# EVB-ANNA-B5_SCHEM_0002_ANNA_Module.net
KiCad netlist of a schematic drawn in Altium Designer
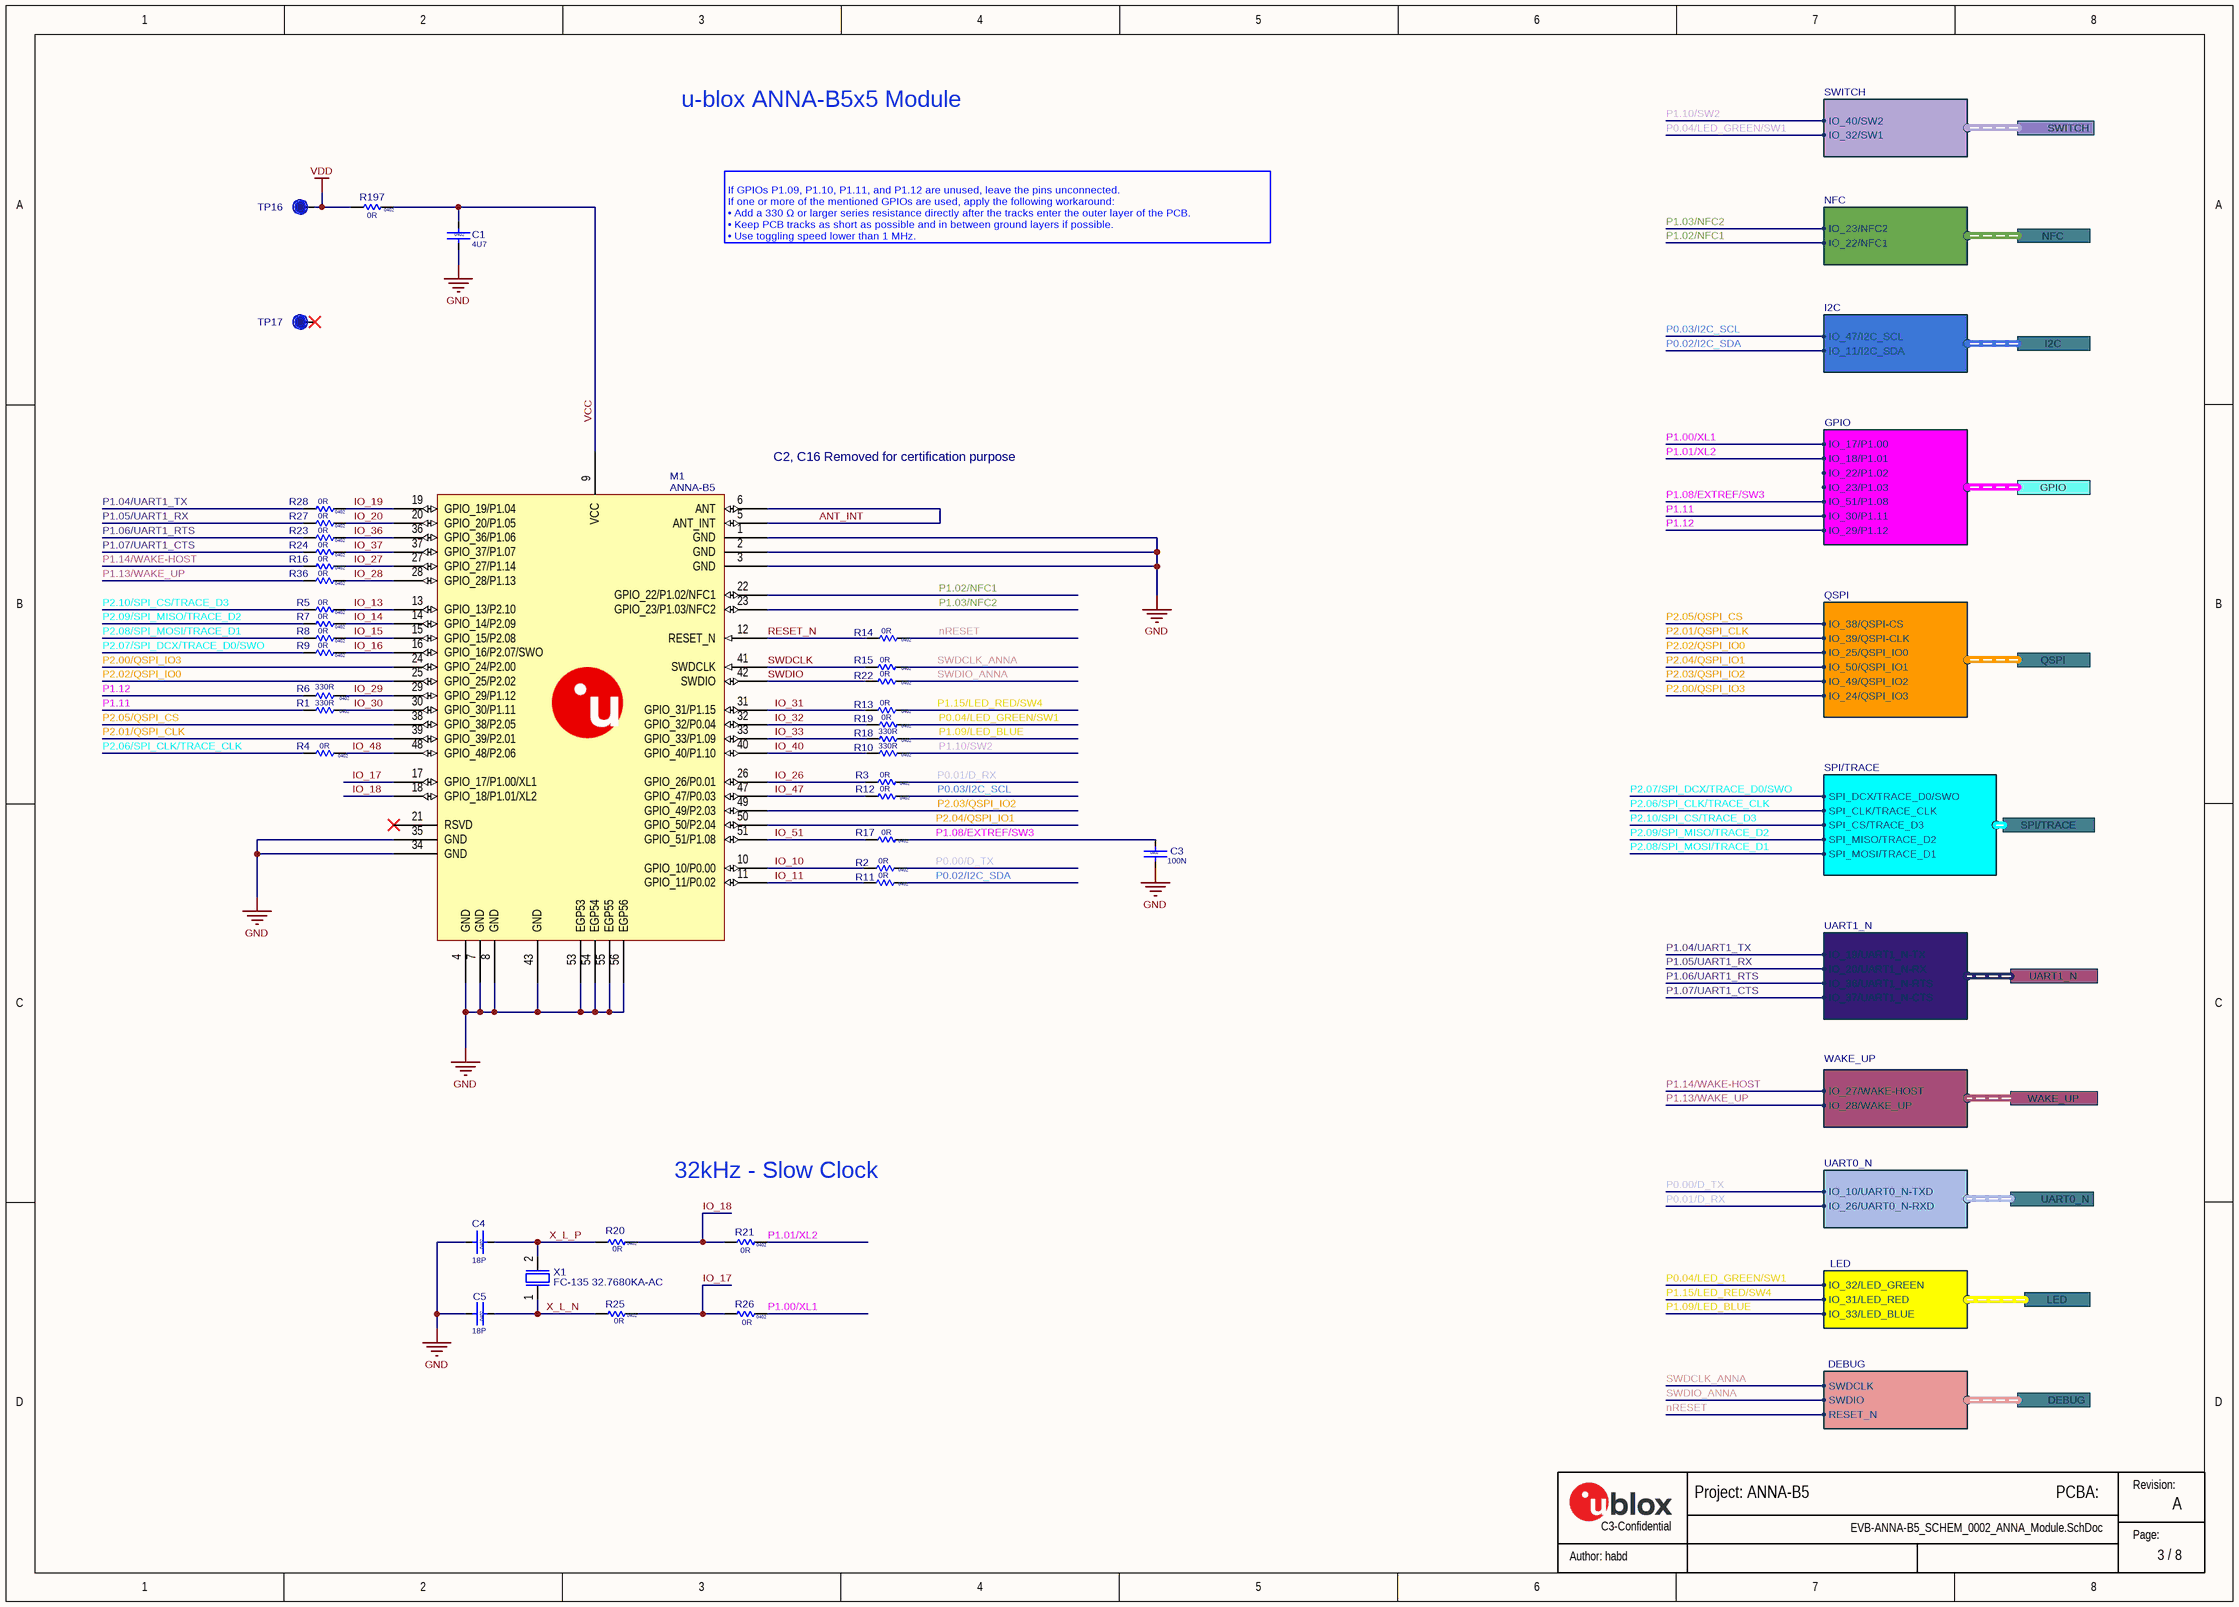
[diagram p0: EVB-ANNA-B5_SCHEM_0002_ANNA_Module.SchDoc]

(export (version "E")
  (design (tool "Eeschema 10.0.6"))
  (components
    (comp (ref "C1")
      (value "4U7")
      (footprint "Cap 0402 HD")
      (description "CAP CER X5R 0402 4U7 20% 10V")
      (fields
        (field (name "SIZE") "0402")
        (field (name "PART NUMBER") "UBXH01-0000243")
        (field (name "TOLERANCE") "20%")
        (field (name "EDITOR") "martin.pilik")
        (field (name "RELEASED BY") "fabrice.bret-dibat")
      )
      (libsource (lib "UBX_Parts_DB_Lib") (part "Cap Chip"))
    )
    (comp (ref "C3")
      (value "100N")
      (footprint "Cap 0402 HD")
      (description "CAP CER X5R 0402 100N 10% 10V")
      (fields
        (field (name "SIZE") "0402")
        (field (name "PART NUMBER") "UBXH01-2021002")
        (field (name "TOLERANCE") "10%")
        (field (name "EDITOR") "roland.rust")
        (field (name "RELEASED BY") "roland.rust")
      )
      (libsource (lib "UBX_Parts_DB_Lib") (part "Cap Chip"))
    )
    (comp (ref "C4")
      (value "18P")
      (footprint "Cap_0402_1100Lx600Wx600H_600x600Pad_350G_FLX")
      (description "CAP CER C0G 0402 18P 5% 25V")
      (fields
        (field (name "SIZE") "0402")
        (field (name "PART NUMBER") "UBXH01-0004017")
        (field (name "TOLERANCE") "5%")
        (field (name "EDITOR") "doris.zahnd")
        (field (name "RELEASED BY") "daniel.hurni")
      )
      (libsource (lib "UBX_Parts_DB_Lib") (part "Cap Chip"))
    )
    (comp (ref "C5")
      (value "18P")
      (footprint "Cap_0402_1100Lx600Wx600H_600x600Pad_350G_FLX")
      (description "CAP CER C0G 0402 18P 5% 25V")
      (fields
        (field (name "SIZE") "0402")
        (field (name "PART NUMBER") "UBXH01-0004017")
        (field (name "TOLERANCE") "5%")
        (field (name "EDITOR") "doris.zahnd")
        (field (name "RELEASED BY") "daniel.hurni")
      )
      (libsource (lib "UBX_Parts_DB_Lib") (part "Cap Chip"))
    )
    (comp (ref "M1")
      (value "UBXH29-0000036")
      (footprint "ANNA-B5")
      (description "SHORT RANGE BLE AND IEEE802.15.4 SIP MODULE U-BLOX ANNA-B5")
      (fields
        (field (name "MANUFACTURER") "u-blox")
        (field (name "MANUFACTURER P/N") "ANNA-B5")
        (field (name "OWNER") "Yaqin Chen")
      )
      (libsource (lib "UBX_Arena") (part "ANNA-B5"))
    )
    (comp (ref "R1")
      (value "330R")
      (footprint "RES_0402_1100Lx600Wx400H_500x600Pad_400G_FLX")
      (description "RES THICK FILM CHIP 0402 330R 5% 63mW")
      (fields
        (field (name "SIZE") "0402")
        (field (name "PART NUMBER") "UBXH18-0008037")
        (field (name "TOLERANCE") "5%")
        (field (name "EDITOR") "daniel.hurni")
        (field (name "RELEASED BY") "doris.zahnd")
      )
      (libsource (lib "UBX_Parts_DB_Lib") (part "Res sm"))
    )
    (comp (ref "R2")
      (value "0R")
      (footprint "RES 0402 HD")
      (description "RES THICK FILM CHIP 0402 0R 0 100mW")
      (fields
        (field (name "SIZE") "0402")
        (field (name "PART NUMBER") "UBXH18-0003002")
        (field (name "TOLERANCE") "0")
        (field (name "EDITOR") "charlotte.biber")
        (field (name "RELEASED BY") "peter.mueller")
      )
      (libsource (lib "UBX_Parts_DB_Lib") (part "Res sm"))
    )
    (comp (ref "R3")
      (value "0R")
      (footprint "RES 0402 HD")
      (description "RES THICK FILM CHIP 0402 0R 0 100mW")
      (fields
        (field (name "SIZE") "0402")
        (field (name "PART NUMBER") "UBXH18-0003002")
        (field (name "TOLERANCE") "0")
        (field (name "EDITOR") "charlotte.biber")
        (field (name "RELEASED BY") "peter.mueller")
      )
      (libsource (lib "UBX_Parts_DB_Lib") (part "Res sm"))
    )
    (comp (ref "R4")
      (value "0R")
      (footprint "RES 0402 HD")
      (description "RES THICK FILM CHIP 0402 0R 0 100mW")
      (fields
        (field (name "SIZE") "0402")
        (field (name "PART NUMBER") "UBXH18-0003002")
        (field (name "TOLERANCE") "0")
        (field (name "EDITOR") "charlotte.biber")
        (field (name "RELEASED BY") "peter.mueller")
      )
      (libsource (lib "UBX_Parts_DB_Lib") (part "Res sm"))
    )
    (comp (ref "R5")
      (value "0R")
      (footprint "RES 0402 HD")
      (description "RES THICK FILM CHIP 0402 0R 0 100mW")
      (fields
        (field (name "SIZE") "0402")
        (field (name "PART NUMBER") "UBXH18-0003002")
        (field (name "TOLERANCE") "0")
        (field (name "EDITOR") "charlotte.biber")
        (field (name "RELEASED BY") "peter.mueller")
      )
      (libsource (lib "UBX_Parts_DB_Lib") (part "Res sm"))
    )
    (comp (ref "R6")
      (value "330R")
      (footprint "RES_0402_1100Lx600Wx400H_500x600Pad_400G_FLX")
      (description "RES THICK FILM CHIP 0402 330R 5% 63mW")
      (fields
        (field (name "SIZE") "0402")
        (field (name "PART NUMBER") "UBXH18-0008037")
        (field (name "TOLERANCE") "5%")
        (field (name "EDITOR") "daniel.hurni")
        (field (name "RELEASED BY") "doris.zahnd")
      )
      (libsource (lib "UBX_Parts_DB_Lib") (part "Res sm"))
    )
    (comp (ref "R7")
      (value "0R")
      (footprint "RES 0402 HD")
      (description "RES THICK FILM CHIP 0402 0R 0 100mW")
      (fields
        (field (name "SIZE") "0402")
        (field (name "PART NUMBER") "UBXH18-0003002")
        (field (name "TOLERANCE") "0")
        (field (name "EDITOR") "charlotte.biber")
        (field (name "RELEASED BY") "peter.mueller")
      )
      (libsource (lib "UBX_Parts_DB_Lib") (part "Res sm"))
    )
    (comp (ref "R8")
      (value "0R")
      (footprint "RES 0402 HD")
      (description "RES THICK FILM CHIP 0402 0R 0 100mW")
      (fields
        (field (name "SIZE") "0402")
        (field (name "PART NUMBER") "UBXH18-0003002")
        (field (name "TOLERANCE") "0")
        (field (name "EDITOR") "charlotte.biber")
        (field (name "RELEASED BY") "peter.mueller")
      )
      (libsource (lib "UBX_Parts_DB_Lib") (part "Res sm"))
    )
    (comp (ref "R9")
      (value "0R")
      (footprint "RES 0402 HD")
      (description "RES THICK FILM CHIP 0402 0R 0 100mW")
      (fields
        (field (name "SIZE") "0402")
        (field (name "PART NUMBER") "UBXH18-0003002")
        (field (name "TOLERANCE") "0")
        (field (name "EDITOR") "charlotte.biber")
        (field (name "RELEASED BY") "peter.mueller")
      )
      (libsource (lib "UBX_Parts_DB_Lib") (part "Res sm"))
    )
    (comp (ref "R10")
      (value "330R")
      (footprint "RES_0402_1100Lx600Wx400H_500x600Pad_400G_FLX")
      (description "RES THICK FILM CHIP 0402 330R 5% 63mW")
      (fields
        (field (name "SIZE") "0402")
        (field (name "PART NUMBER") "UBXH18-0008037")
        (field (name "TOLERANCE") "5%")
        (field (name "EDITOR") "daniel.hurni")
        (field (name "RELEASED BY") "doris.zahnd")
      )
      (libsource (lib "UBX_Parts_DB_Lib") (part "Res sm"))
    )
    (comp (ref "R11")
      (value "0R")
      (footprint "RES 0402 HD")
      (description "RES THICK FILM CHIP 0402 0R 0 100mW")
      (fields
        (field (name "SIZE") "0402")
        (field (name "PART NUMBER") "UBXH18-0003002")
        (field (name "TOLERANCE") "0")
        (field (name "EDITOR") "charlotte.biber")
        (field (name "RELEASED BY") "peter.mueller")
      )
      (libsource (lib "UBX_Parts_DB_Lib") (part "Res sm"))
    )
    (comp (ref "R12")
      (value "0R")
      (footprint "RES_0402_1100Lx600Wx400H_500x600Pad_400G_FLX")
      (description "RES THICK FILM CHIP 0402 0R 0 100mW")
      (fields
        (field (name "SIZE") "0402")
        (field (name "PART NUMBER") "UBXH18-0003002")
        (field (name "TOLERANCE") "0")
        (field (name "EDITOR") "charlotte.biber")
        (field (name "RELEASED BY") "peter.mueller")
      )
      (libsource (lib "UBX_Parts_DB_Lib") (part "Res sm"))
    )
    (comp (ref "R13")
      (value "0R")
      (footprint "RES_0402_1100Lx600Wx400H_500x600Pad_400G_FLX")
      (description "RES THICK FILM CHIP 0402 0R 0 100mW")
      (fields
        (field (name "SIZE") "0402")
        (field (name "PART NUMBER") "UBXH18-0003002")
        (field (name "TOLERANCE") "0")
        (field (name "EDITOR") "charlotte.biber")
        (field (name "RELEASED BY") "peter.mueller")
      )
      (libsource (lib "UBX_Parts_DB_Lib") (part "Res sm"))
    )
    (comp (ref "R14")
      (value "0R")
      (footprint "RES_0402_1100Lx600Wx400H_500x600Pad_400G_FLX")
      (description "RES THICK FILM CHIP 0402 0R 0 100mW")
      (fields
        (field (name "SIZE") "0402")
        (field (name "PART NUMBER") "UBXH18-0003002")
        (field (name "TOLERANCE") "0")
        (field (name "EDITOR") "charlotte.biber")
        (field (name "RELEASED BY") "peter.mueller")
      )
      (libsource (lib "UBX_Parts_DB_Lib") (part "Res sm"))
    )
    (comp (ref "R15")
      (value "0R")
      (footprint "RES 0402 HD")
      (description "RES THICK FILM CHIP 0402 0R 0 100mW")
      (fields
        (field (name "SIZE") "0402")
        (field (name "PART NUMBER") "UBXH18-0003002")
        (field (name "TOLERANCE") "0")
        (field (name "EDITOR") "charlotte.biber")
        (field (name "RELEASED BY") "peter.mueller")
      )
      (libsource (lib "UBX_Parts_DB_Lib") (part "Res sm"))
    )
    (comp (ref "R16")
      (value "0R")
      (footprint "RES 0402 HD")
      (description "RES THICK FILM CHIP 0402 0R 0 100mW")
      (fields
        (field (name "SIZE") "0402")
        (field (name "PART NUMBER") "UBXH18-0003002")
        (field (name "TOLERANCE") "0")
        (field (name "EDITOR") "charlotte.biber")
        (field (name "RELEASED BY") "peter.mueller")
      )
      (libsource (lib "UBX_Parts_DB_Lib") (part "Res sm"))
    )
    (comp (ref "R17")
      (value "0R")
      (footprint "RES 0402 HD")
      (description "RES THICK FILM CHIP 0402 0R 0 100mW")
      (fields
        (field (name "SIZE") "0402")
        (field (name "PART NUMBER") "UBXH18-0003002")
        (field (name "TOLERANCE") "0")
        (field (name "EDITOR") "charlotte.biber")
        (field (name "RELEASED BY") "peter.mueller")
      )
      (libsource (lib "UBX_Parts_DB_Lib") (part "Res sm"))
    )
    (comp (ref "R18")
      (value "330R")
      (footprint "RES_0402_1100Lx600Wx400H_500x600Pad_400G_FLX")
      (description "RES THICK FILM CHIP 0402 330R 5% 63mW")
      (fields
        (field (name "SIZE") "0402")
        (field (name "PART NUMBER") "UBXH18-0008037")
        (field (name "TOLERANCE") "5%")
        (field (name "EDITOR") "daniel.hurni")
        (field (name "RELEASED BY") "doris.zahnd")
      )
      (libsource (lib "UBX_Parts_DB_Lib") (part "Res sm"))
    )
    (comp (ref "R19")
      (value "0R")
      (footprint "RES 0402 HD")
      (description "RES THICK FILM CHIP 0402 0R 0 100mW")
      (fields
        (field (name "SIZE") "0402")
        (field (name "PART NUMBER") "UBXH18-0003002")
        (field (name "TOLERANCE") "0")
        (field (name "EDITOR") "charlotte.biber")
        (field (name "RELEASED BY") "peter.mueller")
      )
      (libsource (lib "UBX_Parts_DB_Lib") (part "Res sm"))
    )
    (comp (ref "R20")
      (value "0R")
      (footprint "RES 0402 HD")
      (description "RES THICK FILM CHIP 0402 0R 0 100mW")
      (fields
        (field (name "SIZE") "0402")
        (field (name "PART NUMBER") "UBXH18-0003002")
        (field (name "TOLERANCE") "0")
        (field (name "EDITOR") "charlotte.biber")
        (field (name "RELEASED BY") "peter.mueller")
      )
      (libsource (lib "UBX_Parts_DB_Lib") (part "Res sm"))
    )
    (comp (ref "R21")
      (value "0R")
      (footprint "RES_0402_1100Lx600Wx400H_500x600Pad_400G_FLX")
      (description "RES THICK FILM CHIP 0402 0R 0 100mW")
      (fields
        (field (name "SIZE") "0402")
        (field (name "PART NUMBER") "UBXH18-0003002")
        (field (name "TOLERANCE") "0")
        (field (name "EDITOR") "charlotte.biber")
        (field (name "RELEASED BY") "peter.mueller")
      )
      (libsource (lib "UBX_Parts_DB_Lib") (part "Res sm"))
    )
    (comp (ref "R22")
      (value "0R")
      (footprint "RES 0402 HD")
      (description "RES THICK FILM CHIP 0402 0R 0 100mW")
      (fields
        (field (name "SIZE") "0402")
        (field (name "PART NUMBER") "UBXH18-0003002")
        (field (name "TOLERANCE") "0")
        (field (name "EDITOR") "charlotte.biber")
        (field (name "RELEASED BY") "peter.mueller")
      )
      (libsource (lib "UBX_Parts_DB_Lib") (part "Res sm"))
    )
    (comp (ref "R23")
      (value "0R")
      (footprint "RES 0402 HD")
      (description "RES THICK FILM CHIP 0402 0R 0 100mW")
      (fields
        (field (name "SIZE") "0402")
        (field (name "PART NUMBER") "UBXH18-0003002")
        (field (name "TOLERANCE") "0")
        (field (name "EDITOR") "charlotte.biber")
        (field (name "RELEASED BY") "peter.mueller")
      )
      (libsource (lib "UBX_Parts_DB_Lib") (part "Res sm"))
    )
    (comp (ref "R24")
      (value "0R")
      (footprint "RES 0402 HD")
      (description "RES THICK FILM CHIP 0402 0R 0 100mW")
      (fields
        (field (name "SIZE") "0402")
        (field (name "PART NUMBER") "UBXH18-0003002")
        (field (name "TOLERANCE") "0")
        (field (name "EDITOR") "charlotte.biber")
        (field (name "RELEASED BY") "peter.mueller")
      )
      (libsource (lib "UBX_Parts_DB_Lib") (part "Res sm"))
    )
    (comp (ref "R25")
      (value "0R")
      (footprint "RES 0402 HD")
      (description "RES THICK FILM CHIP 0402 0R 0 100mW")
      (fields
        (field (name "SIZE") "0402")
        (field (name "PART NUMBER") "UBXH18-0003002")
        (field (name "TOLERANCE") "0")
        (field (name "EDITOR") "charlotte.biber")
        (field (name "RELEASED BY") "peter.mueller")
      )
      (libsource (lib "UBX_Parts_DB_Lib") (part "Res sm"))
    )
    (comp (ref "R26")
      (value "0R")
      (footprint "RES_0402_1100Lx600Wx400H_500x600Pad_400G_FLX")
      (description "RES THICK FILM CHIP 0402 0R 0 100mW")
      (fields
        (field (name "SIZE") "0402")
        (field (name "PART NUMBER") "UBXH18-0003002")
        (field (name "TOLERANCE") "0")
        (field (name "EDITOR") "charlotte.biber")
        (field (name "RELEASED BY") "peter.mueller")
      )
      (libsource (lib "UBX_Parts_DB_Lib") (part "Res sm"))
    )
    (comp (ref "R27")
      (value "0R")
      (footprint "RES 0402 HD")
      (description "RES THICK FILM CHIP 0402 0R 0 100mW")
      (fields
        (field (name "SIZE") "0402")
        (field (name "PART NUMBER") "UBXH18-0003002")
        (field (name "TOLERANCE") "0")
        (field (name "EDITOR") "charlotte.biber")
        (field (name "RELEASED BY") "peter.mueller")
      )
      (libsource (lib "UBX_Parts_DB_Lib") (part "Res sm"))
    )
    (comp (ref "R28")
      (value "0R")
      (footprint "RES 0402 HD")
      (description "RES THICK FILM CHIP 0402 0R 0 100mW")
      (fields
        (field (name "SIZE") "0402")
        (field (name "PART NUMBER") "UBXH18-0003002")
        (field (name "TOLERANCE") "0")
        (field (name "EDITOR") "charlotte.biber")
        (field (name "RELEASED BY") "peter.mueller")
      )
      (libsource (lib "UBX_Parts_DB_Lib") (part "Res sm"))
    )
    (comp (ref "R36")
      (value "0R")
      (footprint "RES_0402_1100Lx600Wx400H_500x600Pad_400G_FLX")
      (description "RES THICK FILM CHIP 0402 0R 0 100mW")
      (fields
        (field (name "SIZE") "0402")
        (field (name "PART NUMBER") "UBXH18-0003002")
        (field (name "TOLERANCE") "0")
        (field (name "EDITOR") "charlotte.biber")
        (field (name "RELEASED BY") "peter.mueller")
      )
      (libsource (lib "UBX_Parts_DB_Lib") (part "Res sm"))
    )
    (comp (ref "R197")
      (value "0R")
      (footprint "RES 0402 HD")
      (description "RES THICK FILM CHIP 0402 0R 0 100mW")
      (fields
        (field (name "SIZE") "0402")
        (field (name "PART NUMBER") "UBXH18-0003002")
        (field (name "TOLERANCE") "0")
        (field (name "EDITOR") "charlotte.biber")
        (field (name "RELEASED BY") "peter.mueller")
      )
      (libsource (lib "UBX_Parts_DB_Lib") (part "Res sm"))
    )
    (comp (ref "TP16")
      (value "TP10R")
      (footprint "TP10R")
      (description "Testpoint, Round 1.0mm Dia")
      (fields (field (name "ADDED BY") "Jeremy D") (field (name "CHECKED BY") "Paul B"))
      (libsource (lib "LEGACY_Rigado_AltiumLib") (part "TP_R"))
    )
    (comp (ref "TP17")
      (value "TP10R")
      (footprint "TP10R")
      (description "Testpoint, Round 1.0mm Dia")
      (fields (field (name "ADDED BY") "Jeremy D") (field (name "CHECKED BY") "Paul B"))
      (libsource (lib "LEGACY_Rigado_AltiumLib") (part "TP_R"))
    )
    (comp (ref "X1")
      (value "UBXH21-0008104")
      (footprint "XTAL_3215")
      (description "CRYSTAL CL=9PF EPSON FC-135 NI/SN TERMINATION 32.768KHz")
      (fields (field (name "MANUFACTURER P/N") "FC-135 32.7680KA-AC") (field (name "OWNER") "Andreas Thiel"))
      (libsource (lib "UBX_Arena") (part "XTAL_2Pin"))
    )
  )
  (nets
    (net (code "12") (name "/ANT_INT") (class "Default")
      (node (ref "M1") (pin "5") (pinfunction "ANT_INT_5") (pintype "bidirectional"))
      (node (ref "M1") (pin "6") (pinfunction "ANT_6") (pintype "bidirectional"))
    )
    (net (code "13") (name "/IO_10") (class "Default")
      (node (ref "M1") (pin "10") (pinfunction "GPIO_10/P0.00_10") (pintype "bidirectional"))
      (node (ref "R2") (pin "2") (pinfunction "2_2") (pintype "passive"))
    )
    (net (code "14") (name "/IO_11") (class "Default")
      (node (ref "M1") (pin "11") (pinfunction "GPIO_11/P0.02_11") (pintype "bidirectional"))
      (node (ref "R11") (pin "1") (pinfunction "1_1") (pintype "passive"))
    )
    (net (code "15") (name "/IO_13") (class "Default")
      (node (ref "M1") (pin "13") (pinfunction "GPIO_13/P2.10_13") (pintype "bidirectional"))
      (node (ref "R5") (pin "2") (pinfunction "2_2") (pintype "passive"))
    )
    (net (code "16") (name "/IO_14") (class "Default")
      (node (ref "M1") (pin "14") (pinfunction "GPIO_14/P2.09_14") (pintype "bidirectional"))
      (node (ref "R7") (pin "2") (pinfunction "2_2") (pintype "passive"))
    )
    (net (code "17") (name "/IO_15") (class "Default")
      (node (ref "M1") (pin "15") (pinfunction "GPIO_15/P2.08_15") (pintype "bidirectional"))
      (node (ref "R8") (pin "2") (pinfunction "2_2") (pintype "passive"))
    )
    (net (code "18") (name "/IO_16") (class "Default")
      (node (ref "M1") (pin "16") (pinfunction "GPIO_16/P2.07/SWO_16") (pintype "bidirectional"))
      (node (ref "R9") (pin "2") (pinfunction "2_2") (pintype "passive"))
    )
    (net (code "19") (name "/IO_17") (class "Default")
      (node (ref "M1") (pin "17") (pinfunction "GPIO_17/P1.00/XL1_17") (pintype "bidirectional"))
      (node (ref "R25") (pin "2") (pinfunction "2_2") (pintype "passive"))
      (node (ref "R26") (pin "2") (pinfunction "2_2") (pintype "passive"))
    )
    (net (code "20") (name "/IO_18") (class "Default")
      (node (ref "M1") (pin "18") (pinfunction "GPIO_18/P1.01/XL2_18") (pintype "bidirectional"))
      (node (ref "R20") (pin "2") (pinfunction "2_2") (pintype "passive"))
      (node (ref "R21") (pin "2") (pinfunction "2_2") (pintype "passive"))
    )
    (net (code "21") (name "/IO_19") (class "Default")
      (node (ref "M1") (pin "19") (pinfunction "GPIO_19/P1.04_19") (pintype "bidirectional"))
      (node (ref "R28") (pin "1") (pinfunction "1_1") (pintype "passive"))
    )
    (net (code "22") (name "/IO_20") (class "Default")
      (node (ref "M1") (pin "20") (pinfunction "GPIO_20/P1.05_20") (pintype "bidirectional"))
      (node (ref "R27") (pin "1") (pinfunction "1_1") (pintype "passive"))
    )
    (net (code "23") (name "/IO_26") (class "Default")
      (node (ref "M1") (pin "26") (pinfunction "GPIO_26/P0.01_26") (pintype "bidirectional"))
      (node (ref "R3") (pin "2") (pinfunction "2_2") (pintype "passive"))
    )
    (net (code "24") (name "/IO_27") (class "Default")
      (node (ref "M1") (pin "27") (pinfunction "GPIO_27/P1.14_27") (pintype "bidirectional"))
      (node (ref "R16") (pin "2") (pinfunction "2_2") (pintype "passive"))
    )
    (net (code "25") (name "/IO_28") (class "Default")
      (node (ref "M1") (pin "28") (pinfunction "GPIO_28/P1.13_28") (pintype "bidirectional"))
      (node (ref "R36") (pin "1") (pinfunction "1_1") (pintype "passive"))
    )
    (net (code "26") (name "/IO_29") (class "Default")
      (node (ref "M1") (pin "29") (pinfunction "GPIO_29/P1.12_29") (pintype "bidirectional"))
      (node (ref "R6") (pin "2") (pinfunction "2_2") (pintype "passive"))
    )
    (net (code "27") (name "/IO_30") (class "Default")
      (node (ref "M1") (pin "30") (pinfunction "GPIO_30/P1.11_30") (pintype "bidirectional"))
      (node (ref "R1") (pin "2") (pinfunction "2_2") (pintype "passive"))
    )
    (net (code "28") (name "/IO_31") (class "Default")
      (node (ref "M1") (pin "31") (pinfunction "GPIO_31/P1.15_31") (pintype "bidirectional"))
      (node (ref "R13") (pin "1") (pinfunction "1_1") (pintype "passive"))
    )
    (net (code "29") (name "/IO_32") (class "Default")
      (node (ref "M1") (pin "32") (pinfunction "GPIO_32/P0.04_32") (pintype "bidirectional"))
      (node (ref "R19") (pin "1") (pinfunction "1_1") (pintype "passive"))
    )
    (net (code "30") (name "/IO_33") (class "Default")
      (node (ref "M1") (pin "33") (pinfunction "GPIO_33/P1.09_33") (pintype "bidirectional"))
      (node (ref "R18") (pin "2") (pinfunction "2_2") (pintype "passive"))
    )
    (net (code "31") (name "/IO_36") (class "Default")
      (node (ref "M1") (pin "36") (pinfunction "GPIO_36/P1.06_36") (pintype "bidirectional"))
      (node (ref "R23") (pin "2") (pinfunction "2_2") (pintype "passive"))
    )
    (net (code "32") (name "/IO_37") (class "Default")
      (node (ref "M1") (pin "37") (pinfunction "GPIO_37/P1.07_37") (pintype "bidirectional"))
      (node (ref "R24") (pin "2") (pinfunction "2_2") (pintype "passive"))
    )
    (net (code "33") (name "/IO_40") (class "Default")
      (node (ref "M1") (pin "40") (pinfunction "GPIO_40/P1.10_40") (pintype "bidirectional"))
      (node (ref "R10") (pin "2") (pinfunction "2_2") (pintype "passive"))
    )
    (net (code "34") (name "/IO_47") (class "Default")
      (node (ref "M1") (pin "47") (pinfunction "GPIO_47/P0.03_47") (pintype "bidirectional"))
      (node (ref "R12") (pin "1") (pinfunction "1_1") (pintype "passive"))
    )
    (net (code "35") (name "/IO_48") (class "Default")
      (node (ref "M1") (pin "48") (pinfunction "GPIO_48/P2.06_48") (pintype "bidirectional"))
      (node (ref "R4") (pin "2") (pinfunction "2_2") (pintype "passive"))
    )
    (net (code "36") (name "/IO_51") (class "Default")
      (node (ref "M1") (pin "51") (pinfunction "GPIO_51/P1.08_51") (pintype "bidirectional"))
      (node (ref "R17") (pin "2") (pinfunction "2_2") (pintype "passive"))
    )
    (net (code "37") (name "/P0.00{slash}D_TX") (class "Default")
      (node (ref "R2") (pin "1") (pinfunction "1_1") (pintype "passive"))
    )
    (net (code "38") (name "/P0.01{slash}D_RX") (class "Default")
      (node (ref "R3") (pin "1") (pinfunction "1_1") (pintype "passive"))
    )
    (net (code "39") (name "/P0.02{slash}I2C_SDA") (class "Default")
      (node (ref "R11") (pin "2") (pinfunction "2_2") (pintype "passive"))
    )
    (net (code "40") (name "/P0.03{slash}I2C_SCL") (class "Default")
      (node (ref "R12") (pin "2") (pinfunction "2_2") (pintype "passive"))
    )
    (net (code "41") (name "/P0.04{slash}LED_GREEN{slash}SW1") (class "Default")
      (node (ref "R19") (pin "2") (pinfunction "2_2") (pintype "passive"))
    )
    (net (code "42") (name "/P1.00{slash}XL1") (class "Default")
      (node (ref "R26") (pin "1") (pinfunction "1_1") (pintype "passive"))
    )
    (net (code "43") (name "/P1.01{slash}XL2") (class "Default")
      (node (ref "R21") (pin "1") (pinfunction "1_1") (pintype "passive"))
    )
    (net (code "44") (name "/P1.02{slash}NFC1") (class "Default")
      (node (ref "M1") (pin "22") (pinfunction "GPIO_22/P1.02/NFC1_22") (pintype "bidirectional"))
    )
    (net (code "45") (name "/P1.03{slash}NFC2") (class "Default")
      (node (ref "M1") (pin "23") (pinfunction "GPIO_23/P1.03/NFC2_23") (pintype "bidirectional"))
    )
    (net (code "46") (name "/P1.04{slash}UART1_TX") (class "Default")
      (node (ref "R28") (pin "2") (pinfunction "2_2") (pintype "passive"))
    )
    (net (code "47") (name "/P1.05{slash}UART1_RX") (class "Default")
      (node (ref "R27") (pin "2") (pinfunction "2_2") (pintype "passive"))
    )
    (net (code "48") (name "/P1.06{slash}UART1_RTS") (class "Default")
      (node (ref "R23") (pin "1") (pinfunction "1_1") (pintype "passive"))
    )
    (net (code "49") (name "/P1.07{slash}UART1_CTS") (class "Default")
      (node (ref "R24") (pin "1") (pinfunction "1_1") (pintype "passive"))
    )
    (net (code "50") (name "/P1.08{slash}EXTREF{slash}SW3") (class "Default")
      (node (ref "C3") (pin "2") (pinfunction "2_2") (pintype "passive"))
      (node (ref "R17") (pin "1") (pinfunction "1_1") (pintype "passive"))
    )
    (net (code "51") (name "/P1.09{slash}LED_BLUE") (class "Default")
      (node (ref "R18") (pin "1") (pinfunction "1_1") (pintype "passive"))
    )
    (net (code "52") (name "/P1.10{slash}SW2") (class "Default")
      (node (ref "R10") (pin "1") (pinfunction "1_1") (pintype "passive"))
    )
    (net (code "53") (name "/P1.11") (class "Default")
      (node (ref "R1") (pin "1") (pinfunction "1_1") (pintype "passive"))
    )
    (net (code "54") (name "/P1.12") (class "Default")
      (node (ref "R6") (pin "1") (pinfunction "1_1") (pintype "passive"))
    )
    (net (code "55") (name "/P1.13{slash}WAKE_UP") (class "Default")
      (node (ref "R36") (pin "2") (pinfunction "2_2") (pintype "passive"))
    )
    (net (code "56") (name "/P1.14{slash}WAKE-HOST") (class "Default")
      (node (ref "R16") (pin "1") (pinfunction "1_1") (pintype "passive"))
    )
    (net (code "57") (name "/P1.15{slash}LED_RED{slash}SW4") (class "Default")
      (node (ref "R13") (pin "2") (pinfunction "2_2") (pintype "passive"))
    )
    (net (code "58") (name "/P2.00{slash}QSPI_IO3") (class "Default")
      (node (ref "M1") (pin "24") (pinfunction "GPIO_24/P2.00_24") (pintype "bidirectional"))
    )
    (net (code "59") (name "/P2.01{slash}QSPI_CLK") (class "Default")
      (node (ref "M1") (pin "39") (pinfunction "GPIO_39/P2.01_39") (pintype "bidirectional"))
    )
    (net (code "60") (name "/P2.02{slash}QSPI_IO0") (class "Default")
      (node (ref "M1") (pin "25") (pinfunction "GPIO_25/P2.02_25") (pintype "bidirectional"))
    )
    (net (code "61") (name "/P2.03{slash}QSPI_IO2") (class "Default")
      (node (ref "M1") (pin "49") (pinfunction "GPIO_49/P2.03_49") (pintype "bidirectional"))
    )
    (net (code "62") (name "/P2.04{slash}QSPI_IO1") (class "Default")
      (node (ref "M1") (pin "50") (pinfunction "GPIO_50/P2.04_50") (pintype "bidirectional"))
    )
    (net (code "63") (name "/P2.05{slash}QSPI_CS") (class "Default")
      (node (ref "M1") (pin "38") (pinfunction "GPIO_38/P2.05_38") (pintype "bidirectional"))
    )
    (net (code "64") (name "/P2.06{slash}SPI_CLK{slash}TRACE_CLK") (class "Default")
      (node (ref "R4") (pin "1") (pinfunction "1_1") (pintype "passive"))
    )
    (net (code "65") (name "/P2.07{slash}SPI_DCX{slash}TRACE_D0{slash}SWO") (class "Default")
      (node (ref "R9") (pin "1") (pinfunction "1_1") (pintype "passive"))
    )
    (net (code "66") (name "/P2.08{slash}SPI_MOSI{slash}TRACE_D1") (class "Default")
      (node (ref "R8") (pin "1") (pinfunction "1_1") (pintype "passive"))
    )
    (net (code "67") (name "/P2.09{slash}SPI_MISO{slash}TRACE_D2") (class "Default")
      (node (ref "R7") (pin "1") (pinfunction "1_1") (pintype "passive"))
    )
    (net (code "68") (name "/P2.10{slash}SPI_CS{slash}TRACE_D3") (class "Default")
      (node (ref "R5") (pin "1") (pinfunction "1_1") (pintype "passive"))
    )
    (net (code "69") (name "/RESET_N") (class "Default")
      (node (ref "M1") (pin "12") (pinfunction "RESET_N_12") (pintype "input"))
      (node (ref "R14") (pin "1") (pinfunction "1_1") (pintype "passive"))
    )
    (net (code "70") (name "/SWDCLK") (class "Default")
      (node (ref "M1") (pin "41") (pinfunction "SWDCLK_41") (pintype "input"))
      (node (ref "R15") (pin "1") (pinfunction "1_1") (pintype "passive"))
    )
    (net (code "71") (name "/SWDCLK_ANNA") (class "Default")
      (node (ref "R15") (pin "2") (pinfunction "2_2") (pintype "passive"))
    )
    (net (code "72") (name "/SWDIO") (class "Default")
      (node (ref "M1") (pin "42") (pinfunction "SWDIO_42") (pintype "bidirectional"))
      (node (ref "R22") (pin "1") (pinfunction "1_1") (pintype "passive"))
    )
    (net (code "73") (name "/SWDIO_ANNA") (class "Default")
      (node (ref "R22") (pin "2") (pinfunction "2_2") (pintype "passive"))
    )
    (net (code "74") (name "/VCC") (class "Default")
      (node (ref "C1") (pin "1") (pinfunction "1_1") (pintype "passive"))
      (node (ref "M1") (pin "9") (pinfunction "VCC_9") (pintype "power_in"))
      (node (ref "R197") (pin "1") (pinfunction "1_1") (pintype "passive"))
    )
    (net (code "75") (name "/X_L_N") (class "Default")
      (node (ref "C5") (pin "1") (pinfunction "1_1") (pintype "passive"))
      (node (ref "R25") (pin "1") (pinfunction "1_1") (pintype "passive"))
      (node (ref "X1") (pin "1") (pintype "passive"))
    )
    (net (code "76") (name "/X_L_P") (class "Default")
      (node (ref "C4") (pin "1") (pinfunction "1_1") (pintype "passive"))
      (node (ref "R20") (pin "1") (pinfunction "1_1") (pintype "passive"))
      (node (ref "X1") (pin "2") (pintype "passive"))
    )
    (net (code "77") (name "/nRESET") (class "Default")
      (node (ref "R14") (pin "2") (pinfunction "2_2") (pintype "passive"))
    )
    (net (code "89") (name "GND") (class "Default")
      (node (ref "C1") (pin "2") (pinfunction "2_2") (pintype "passive"))
      (node (ref "C3") (pin "1") (pinfunction "1_1") (pintype "passive"))
      (node (ref "C4") (pin "2") (pinfunction "2_2") (pintype "passive"))
      (node (ref "C5") (pin "2") (pinfunction "2_2") (pintype "passive"))
      (node (ref "M1") (pin "1") (pinfunction "GND_1") (pintype "power_in"))
      (node (ref "M1") (pin "2") (pinfunction "GND_2") (pintype "power_in"))
      (node (ref "M1") (pin "3") (pinfunction "GND_3") (pintype "power_in"))
      (node (ref "M1") (pin "34") (pinfunction "GND_34") (pintype "power_in"))
      (node (ref "M1") (pin "35") (pinfunction "GND_35") (pintype "power_in"))
      (node (ref "M1") (pin "4") (pinfunction "GND_4") (pintype "power_in"))
      (node (ref "M1") (pin "43") (pinfunction "GND_43") (pintype "power_in"))
      (node (ref "M1") (pin "53") (pinfunction "EGP53_53") (pintype "power_in"))
      (node (ref "M1") (pin "54") (pinfunction "EGP54_54") (pintype "power_in"))
      (node (ref "M1") (pin "55") (pinfunction "EGP55_55") (pintype "power_in"))
      (node (ref "M1") (pin "56") (pinfunction "EGP56_56") (pintype "power_in"))
      (node (ref "M1") (pin "7") (pinfunction "GND_7") (pintype "power_in"))
      (node (ref "M1") (pin "8") (pinfunction "GND_8") (pintype "power_in"))
    )
    (net (code "90") (name "VDD") (class "Default")
      (node (ref "R197") (pin "2") (pinfunction "2_2") (pintype "passive"))
      (node (ref "TP16") (pin "1") (pintype "passive"))
    )
    (net (code "91") (name "unconnected-(M1-RSVD-Pad21)") (class "Default")
      (node (ref "M1") (pin "21") (pinfunction "RSVD_21") (pintype "power_in+no_connect"))
    )
    (net (code "92") (name "unconnected-(TP17-Pad1)") (class "Default")
      (node (ref "TP17") (pin "1") (pintype "passive+no_connect"))
    )
  )
)
